# ClipBoard-V1_1.net
KiCad netlist of a schematic drawn in EAGLE
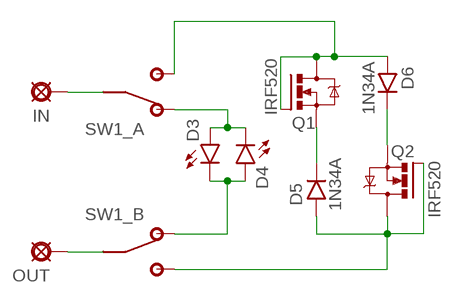
[diagram p0: schematic, sheet 1]

(export (version "E")
  (design (tool "Eeschema 10.0.6"))
  (components
    (comp (ref "D3")
      (value "RED")
      (footprint "eagle-import:LED3MM")
      (libsource (lib "eagle-import") (part "LED3MM"))
    )
    (comp (ref "D4")
      (value "RED")
      (footprint "eagle-import:LED3MM")
      (libsource (lib "eagle-import") (part "LED3MM"))
    )
    (comp (ref "D5")
      (value "1N34A")
      (footprint "eagle-import:DO07")
      (libsource (lib "eagle-import") (part "DO07"))
    )
    (comp (ref "D6")
      (value "1N34A")
      (footprint "eagle-import:DO07")
      (libsource (lib "eagle-import") (part "DO07"))
    )
    (comp (ref "IN")
      (value "CLIPIN")
      (footprint "eagle-import:SQUARE")
      (libsource (lib "eagle-import") (part "PAD"))
    )
    (comp (ref "OUT")
      (value "CLIPOUT")
      (footprint "eagle-import:SQUARE")
      (libsource (lib "eagle-import") (part "PAD"))
    )
    (comp (ref "Q1")
      (value "IRF520")
      (footprint "eagle-import:TO220BV")
      (libsource (lib "eagle-import") (part "IRF520"))
    )
    (comp (ref "Q2")
      (value "IRF520")
      (footprint "eagle-import:TO220BV")
      (libsource (lib "eagle-import") (part "IRF520"))
    )
    (comp (ref "SW1")
      (value "DPDT")
      (footprint "eagle-import:DPDT_PCB")
      (libsource (lib "eagle-import") (part "DPDTDPDT_2"))
    )
  )
  (nets
    (net (code "1") (name "Net-(D3-C)") (class "Default")
      (node (ref "D3") (pin "K") (pinfunction "C_K") (pintype "passive"))
      (node (ref "D4") (pin "A") (pinfunction "A_A") (pintype "passive"))
      (node (ref "SW1") (pin "B2") (pinfunction "1_B2") (pintype "passive"))
    )
    (net (code "2") (name "Net-(D4-C)") (class "Default")
      (node (ref "D3") (pin "A") (pinfunction "A_A") (pintype "passive"))
      (node (ref "D4") (pin "K") (pinfunction "C_K") (pintype "passive"))
      (node (ref "SW1") (pin "A2") (pinfunction "1_A2") (pintype "passive"))
    )
    (net (code "3") (name "Net-(D5-PadC)") (class "Default")
      (node (ref "D5") (pin "C") (pinfunction "C_C") (pintype "passive"))
      (node (ref "Q1") (pin "S") (pinfunction "S_S") (pintype "passive"))
    )
    (net (code "4") (name "Net-(D6-PadC)") (class "Default")
      (node (ref "D6") (pin "C") (pinfunction "C_C") (pintype "passive"))
      (node (ref "Q2") (pin "S") (pinfunction "S_S") (pintype "passive"))
    )
    (net (code "5") (name "Net-(IN-PAD)") (class "Default")
      (node (ref "IN") (pin "1") (pinfunction "PAD_1") (pintype "passive"))
      (node (ref "SW1") (pin "A1") (pinfunction "2_A1") (pintype "passive"))
    )
    (net (code "6") (name "Net-(OUT-PAD)") (class "Default")
      (node (ref "OUT") (pin "1") (pinfunction "PAD_1") (pintype "passive"))
      (node (ref "SW1") (pin "B1") (pinfunction "2_B1") (pintype "passive"))
    )
    (net (code "7") (name "Net-(SW1A-3)") (class "Default")
      (node (ref "D6") (pin "A") (pinfunction "A_A") (pintype "passive"))
      (node (ref "Q1") (pin "D") (pinfunction "D_D") (pintype "passive"))
      (node (ref "Q1") (pin "G") (pinfunction "G_G") (pintype "passive"))
      (node (ref "SW1") (pin "A3") (pinfunction "3_A3") (pintype "passive"))
    )
    (net (code "8") (name "Net-(SW1B-3)") (class "Default")
      (node (ref "D5") (pin "A") (pinfunction "A_A") (pintype "passive"))
      (node (ref "Q2") (pin "D") (pinfunction "D_D") (pintype "passive"))
      (node (ref "Q2") (pin "G") (pinfunction "G_G") (pintype "passive"))
      (node (ref "SW1") (pin "B3") (pinfunction "3_B3") (pintype "passive"))
    )
  )
)
